# minimumSystem_Dio_Faziko_Pratama.net
KiCad netlist of a schematic drawn in EAGLE
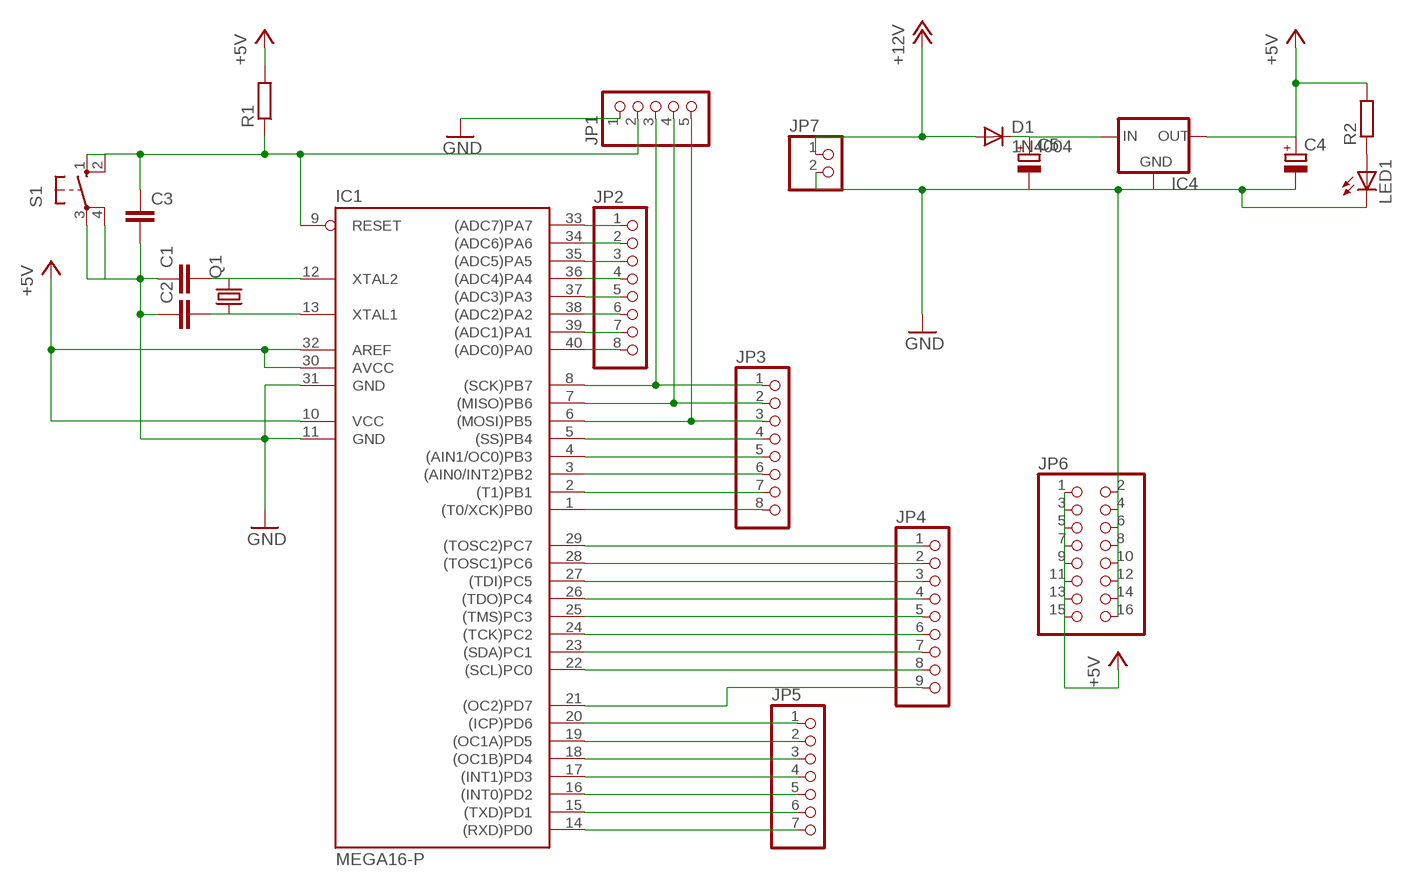
[diagram p0: schematic, sheet 1]

(export (version "E")
  (design (tool "Eeschema 10.0.6"))
  (components
    (comp (ref "C1")
      (value "C-EU025-024X044")
      (footprint "eagle-import:C025-024X044")
      (libsource (lib "eagle-import") (part "C-EU025-024X044"))
    )
    (comp (ref "C2")
      (value "C-EU025-024X044")
      (footprint "eagle-import:C025-024X044")
      (libsource (lib "eagle-import") (part "C-EU025-024X044"))
    )
    (comp (ref "C3")
      (value "C-EU050-025X075")
      (footprint "eagle-import:C050-025X075")
      (libsource (lib "eagle-import") (part "resistor_C-EU050-025X075"))
    )
    (comp (ref "C4")
      (value "CPOL-EUE2.5-5")
      (footprint "eagle-import:E2,5-5")
      (libsource (lib "eagle-import") (part "CPOL-EUE2.5-5"))
    )
    (comp (ref "C5")
      (value "CPOL-EUE2.5-5")
      (footprint "eagle-import:E2,5-5")
      (libsource (lib "eagle-import") (part "CPOL-EUE2.5-5"))
    )
    (comp (ref "D1")
      (value "1N4004")
      (footprint "eagle-import:DO41-10")
      (libsource (lib "eagle-import") (part "1N4004"))
    )
    (comp (ref "IC1")
      (value "MEGA16-P")
      (footprint "eagle-import:DIL40")
      (fields (field (name "MPN") "ATMEGA16-16PU"))
      (libsource (lib "eagle-import") (part "MEGA16-P"))
    )
    (comp (ref "IC4")
      (value "78XXS")
      (footprint "eagle-import:78XXS")
      (libsource (lib "eagle-import") (part "78XXS"))
    )
    (comp (ref "JP1")
      (value "PINHD-1X5")
      (footprint "eagle-import:1X05")
      (libsource (lib "eagle-import") (part "PINHD-1X5"))
    )
    (comp (ref "JP2")
      (value "PINHD-1X8")
      (footprint "eagle-import:1X08")
      (libsource (lib "eagle-import") (part "PINHD-1X8"))
    )
    (comp (ref "JP3")
      (value "PINHD-1X8")
      (footprint "eagle-import:1X08")
      (libsource (lib "eagle-import") (part "PINHD-1X8"))
    )
    (comp (ref "JP4")
      (value "PINHD-1X9")
      (footprint "eagle-import:1X09")
      (libsource (lib "eagle-import") (part "PINHD-1X9"))
    )
    (comp (ref "JP5")
      (value "PINHD-1X7")
      (footprint "eagle-import:1X07")
      (libsource (lib "eagle-import") (part "PINHD-1X7"))
    )
    (comp (ref "JP6")
      (value "PINHD-2X8")
      (footprint "eagle-import:2X08")
      (libsource (lib "eagle-import") (part "PINHD-2X8"))
    )
    (comp (ref "JP7")
      (value "PINHD-1X2")
      (footprint "eagle-import:1X02")
      (libsource (lib "eagle-import") (part "PINHD-1X2"))
    )
    (comp (ref "LED1")
      (value "LED5MM")
      (footprint "eagle-import:LED5MM")
      (libsource (lib "eagle-import") (part "LED5MM"))
    )
    (comp (ref "Q1")
      (value "CRYSTALHC49U-V")
      (footprint "eagle-import:HC49U-V")
      (libsource (lib "eagle-import") (part "CRYSTALHC49U-V"))
    )
    (comp (ref "R1")
      (value "R-EU_0204/7")
      (footprint "eagle-import:0204_7")
      (libsource (lib "eagle-import") (part "R-EU_0204/7"))
    )
    (comp (ref "R2")
      (value "R-EU_0204/7")
      (footprint "eagle-import:0204_7")
      (libsource (lib "eagle-import") (part "R-EU_0204/7"))
    )
    (comp (ref "S1")
      (value "10-XX")
      (footprint "eagle-import:B3F-10XX")
      (fields (field (name "MPN") "B3F-1000"))
      (libsource (lib "eagle-import") (part "10-XX"))
    )
  )
  (nets
    (net (code "1") (name "+5V") (class "Default")
      (node (ref "C4") (pin "+") (pinfunction "+_+") (pintype "passive"))
      (node (ref "IC1") (pin "10") (pinfunction "VCC_10") (pintype "power_in"))
      (node (ref "IC1") (pin "30") (pinfunction "AVCC_30") (pintype "power_in"))
      (node (ref "IC1") (pin "32") (pinfunction "AREF_32") (pintype "passive"))
      (node (ref "IC4") (pin "OUT") (pinfunction "OUT_OUT") (pintype "passive"))
      (node (ref "JP6") (pin "1") (pinfunction "1_1") (pintype "passive"))
      (node (ref "JP6") (pin "11") (pinfunction "11_11") (pintype "passive"))
      (node (ref "JP6") (pin "13") (pinfunction "13_13") (pintype "passive"))
      (node (ref "JP6") (pin "15") (pinfunction "15_15") (pintype "passive"))
      (node (ref "JP6") (pin "3") (pinfunction "3_3") (pintype "passive"))
      (node (ref "JP6") (pin "5") (pinfunction "5_5") (pintype "passive"))
      (node (ref "JP6") (pin "7") (pinfunction "7_7") (pintype "passive"))
      (node (ref "JP6") (pin "9") (pinfunction "9_9") (pintype "passive"))
      (node (ref "R1") (pin "2") (pinfunction "2_2") (pintype "passive"))
      (node (ref "R2") (pin "2") (pinfunction "2_2") (pintype "passive"))
    )
    (net (code "2") (name "+12V") (class "Default")
      (node (ref "D1") (pin "A") (pinfunction "A_A") (pintype "passive"))
      (node (ref "JP7") (pin "1") (pinfunction "1_1") (pintype "passive"))
    )
    (net (code "3") (name "GND") (class "Default")
      (node (ref "C1") (pin "1") (pinfunction "1_1") (pintype "passive"))
      (node (ref "C2") (pin "1") (pinfunction "1_1") (pintype "passive"))
      (node (ref "C3") (pin "2") (pinfunction "2_2") (pintype "passive"))
      (node (ref "C4") (pin "-") (pinfunction "-_-") (pintype "passive"))
      (node (ref "C5") (pin "-") (pinfunction "-_-") (pintype "passive"))
      (node (ref "IC1") (pin "11") (pinfunction "GND_11") (pintype "power_in"))
      (node (ref "IC1") (pin "31") (pinfunction "GND_31") (pintype "power_in"))
      (node (ref "IC4") (pin "GND") (pinfunction "GND_GND") (pintype "input"))
      (node (ref "JP1") (pin "1") (pinfunction "1_1") (pintype "passive"))
      (node (ref "JP6") (pin "10") (pinfunction "10_10") (pintype "passive"))
      (node (ref "JP6") (pin "12") (pinfunction "12_12") (pintype "passive"))
      (node (ref "JP6") (pin "14") (pinfunction "14_14") (pintype "passive"))
      (node (ref "JP6") (pin "16") (pinfunction "16_16") (pintype "passive"))
      (node (ref "JP6") (pin "2") (pinfunction "2_2") (pintype "passive"))
      (node (ref "JP6") (pin "4") (pinfunction "4_4") (pintype "passive"))
      (node (ref "JP6") (pin "6") (pinfunction "6_6") (pintype "passive"))
      (node (ref "JP6") (pin "8") (pinfunction "8_8") (pintype "passive"))
      (node (ref "JP7") (pin "2") (pinfunction "2_2") (pintype "passive"))
      (node (ref "LED1") (pin "K") (pinfunction "C_K") (pintype "passive"))
      (node (ref "S1") (pin "3") (pinfunction "P_3") (pintype "passive"))
      (node (ref "S1") (pin "4") (pinfunction "P1_4") (pintype "passive"))
    )
    (net (code "4") (name "Net-(C5-Pad+)") (class "Default")
      (node (ref "C5") (pin "+") (pinfunction "+_+") (pintype "passive"))
      (node (ref "D1") (pin "C") (pinfunction "C_C") (pintype "passive"))
      (node (ref "IC4") (pin "IN") (pinfunction "IN_IN") (pintype "input"))
    )
    (net (code "5") (name "Net-(IC1-(ADC0)PA0)") (class "Default")
      (node (ref "IC1") (pin "40") (pinfunction "(ADC0)PA0_40") (pintype "bidirectional"))
      (node (ref "JP2") (pin "8") (pinfunction "8_8") (pintype "passive"))
    )
    (net (code "6") (name "Net-(IC1-(ADC1)PA1)") (class "Default")
      (node (ref "IC1") (pin "39") (pinfunction "(ADC1)PA1_39") (pintype "bidirectional"))
      (node (ref "JP2") (pin "7") (pinfunction "7_7") (pintype "passive"))
    )
    (net (code "7") (name "Net-(IC1-(ADC2)PA2)") (class "Default")
      (node (ref "IC1") (pin "38") (pinfunction "(ADC2)PA2_38") (pintype "bidirectional"))
      (node (ref "JP2") (pin "6") (pinfunction "6_6") (pintype "passive"))
    )
    (net (code "8") (name "Net-(IC1-(ADC3)PA3)") (class "Default")
      (node (ref "IC1") (pin "37") (pinfunction "(ADC3)PA3_37") (pintype "bidirectional"))
      (node (ref "JP2") (pin "5") (pinfunction "5_5") (pintype "passive"))
    )
    (net (code "9") (name "Net-(IC1-(ADC4)PA4)") (class "Default")
      (node (ref "IC1") (pin "36") (pinfunction "(ADC4)PA4_36") (pintype "bidirectional"))
      (node (ref "JP2") (pin "4") (pinfunction "4_4") (pintype "passive"))
    )
    (net (code "10") (name "Net-(IC1-(ADC5)PA5)") (class "Default")
      (node (ref "IC1") (pin "35") (pinfunction "(ADC5)PA5_35") (pintype "bidirectional"))
      (node (ref "JP2") (pin "3") (pinfunction "3_3") (pintype "passive"))
    )
    (net (code "11") (name "Net-(IC1-(ADC6)PA6)") (class "Default")
      (node (ref "IC1") (pin "34") (pinfunction "(ADC6)PA6_34") (pintype "bidirectional"))
      (node (ref "JP2") (pin "2") (pinfunction "2_2") (pintype "passive"))
    )
    (net (code "12") (name "Net-(IC1-(ADC7)PA7)") (class "Default")
      (node (ref "IC1") (pin "33") (pinfunction "(ADC7)PA7_33") (pintype "bidirectional"))
      (node (ref "JP2") (pin "1") (pinfunction "1_1") (pintype "passive"))
    )
    (net (code "13") (name "Net-(IC1-(AIN0{slash}INT2)PB2)") (class "Default")
      (node (ref "IC1") (pin "3") (pinfunction "(AIN0/INT2)PB2_3") (pintype "bidirectional"))
      (node (ref "JP3") (pin "6") (pinfunction "6_6") (pintype "passive"))
    )
    (net (code "14") (name "Net-(IC1-(AIN1{slash}OC0)PB3)") (class "Default")
      (node (ref "IC1") (pin "4") (pinfunction "(AIN1/OC0)PB3_4") (pintype "bidirectional"))
      (node (ref "JP3") (pin "5") (pinfunction "5_5") (pintype "passive"))
    )
    (net (code "15") (name "Net-(IC1-(ICP)PD6)") (class "Default")
      (node (ref "IC1") (pin "20") (pinfunction "(ICP)PD6_20") (pintype "bidirectional"))
      (node (ref "JP5") (pin "1") (pinfunction "1_1") (pintype "passive"))
    )
    (net (code "16") (name "Net-(IC1-(INT0)PD2)") (class "Default")
      (node (ref "IC1") (pin "16") (pinfunction "(INT0)PD2_16") (pintype "bidirectional"))
      (node (ref "JP5") (pin "5") (pinfunction "5_5") (pintype "passive"))
    )
    (net (code "17") (name "Net-(IC1-(INT1)PD3)") (class "Default")
      (node (ref "IC1") (pin "17") (pinfunction "(INT1)PD3_17") (pintype "bidirectional"))
      (node (ref "JP5") (pin "4") (pinfunction "4_4") (pintype "passive"))
    )
    (net (code "18") (name "Net-(IC1-(MISO)PB6)") (class "Default")
      (node (ref "IC1") (pin "7") (pinfunction "(MISO)PB6_7") (pintype "bidirectional"))
      (node (ref "JP1") (pin "4") (pinfunction "4_4") (pintype "passive"))
      (node (ref "JP3") (pin "2") (pinfunction "2_2") (pintype "passive"))
    )
    (net (code "19") (name "Net-(IC1-(MOSI)PB5)") (class "Default")
      (node (ref "IC1") (pin "6") (pinfunction "(MOSI)PB5_6") (pintype "bidirectional"))
      (node (ref "JP1") (pin "5") (pinfunction "5_5") (pintype "passive"))
      (node (ref "JP3") (pin "3") (pinfunction "3_3") (pintype "passive"))
    )
    (net (code "20") (name "Net-(IC1-(OC1A)PD5)") (class "Default")
      (node (ref "IC1") (pin "19") (pinfunction "(OC1A)PD5_19") (pintype "bidirectional"))
      (node (ref "JP5") (pin "2") (pinfunction "2_2") (pintype "passive"))
    )
    (net (code "21") (name "Net-(IC1-(OC1B)PD4)") (class "Default")
      (node (ref "IC1") (pin "18") (pinfunction "(OC1B)PD4_18") (pintype "bidirectional"))
      (node (ref "JP5") (pin "3") (pinfunction "3_3") (pintype "passive"))
    )
    (net (code "22") (name "Net-(IC1-(OC2)PD7)") (class "Default")
      (node (ref "IC1") (pin "21") (pinfunction "(OC2)PD7_21") (pintype "bidirectional"))
      (node (ref "JP4") (pin "9") (pinfunction "9_9") (pintype "passive"))
    )
    (net (code "23") (name "Net-(IC1-(RXD)PD0)") (class "Default")
      (node (ref "IC1") (pin "14") (pinfunction "(RXD)PD0_14") (pintype "bidirectional"))
      (node (ref "JP5") (pin "7") (pinfunction "7_7") (pintype "passive"))
    )
    (net (code "24") (name "Net-(IC1-(SCK)PB7)") (class "Default")
      (node (ref "IC1") (pin "8") (pinfunction "(SCK)PB7_8") (pintype "bidirectional"))
      (node (ref "JP1") (pin "3") (pinfunction "3_3") (pintype "passive"))
      (node (ref "JP3") (pin "1") (pinfunction "1_1") (pintype "passive"))
    )
    (net (code "25") (name "Net-(IC1-(SCL)PC0)") (class "Default")
      (node (ref "IC1") (pin "22") (pinfunction "(SCL)PC0_22") (pintype "bidirectional"))
      (node (ref "JP4") (pin "8") (pinfunction "8_8") (pintype "passive"))
    )
    (net (code "26") (name "Net-(IC1-(SDA)PC1)") (class "Default")
      (node (ref "IC1") (pin "23") (pinfunction "(SDA)PC1_23") (pintype "bidirectional"))
      (node (ref "JP4") (pin "7") (pinfunction "7_7") (pintype "passive"))
    )
    (net (code "27") (name "Net-(IC1-(SS)PB4)") (class "Default")
      (node (ref "IC1") (pin "5") (pinfunction "(SS)PB4_5") (pintype "bidirectional"))
      (node (ref "JP3") (pin "4") (pinfunction "4_4") (pintype "passive"))
    )
    (net (code "28") (name "Net-(IC1-(T0{slash}XCK)PB0)") (class "Default")
      (node (ref "IC1") (pin "1") (pinfunction "(T0/XCK)PB0_1") (pintype "bidirectional"))
      (node (ref "JP3") (pin "8") (pinfunction "8_8") (pintype "passive"))
    )
    (net (code "29") (name "Net-(IC1-(T1)PB1)") (class "Default")
      (node (ref "IC1") (pin "2") (pinfunction "(T1)PB1_2") (pintype "bidirectional"))
      (node (ref "JP3") (pin "7") (pinfunction "7_7") (pintype "passive"))
    )
    (net (code "30") (name "Net-(IC1-(TCK)PC2)") (class "Default")
      (node (ref "IC1") (pin "24") (pinfunction "(TCK)PC2_24") (pintype "bidirectional"))
      (node (ref "JP4") (pin "6") (pinfunction "6_6") (pintype "passive"))
    )
    (net (code "31") (name "Net-(IC1-(TDI)PC5)") (class "Default")
      (node (ref "IC1") (pin "27") (pinfunction "(TDI)PC5_27") (pintype "bidirectional"))
      (node (ref "JP4") (pin "3") (pinfunction "3_3") (pintype "passive"))
    )
    (net (code "32") (name "Net-(IC1-(TDO)PC4)") (class "Default")
      (node (ref "IC1") (pin "26") (pinfunction "(TDO)PC4_26") (pintype "bidirectional"))
      (node (ref "JP4") (pin "4") (pinfunction "4_4") (pintype "passive"))
    )
    (net (code "33") (name "Net-(IC1-(TMS)PC3)") (class "Default")
      (node (ref "IC1") (pin "25") (pinfunction "(TMS)PC3_25") (pintype "bidirectional"))
      (node (ref "JP4") (pin "5") (pinfunction "5_5") (pintype "passive"))
    )
    (net (code "34") (name "Net-(IC1-(TOSC1)PC6)") (class "Default")
      (node (ref "IC1") (pin "28") (pinfunction "(TOSC1)PC6_28") (pintype "bidirectional"))
      (node (ref "JP4") (pin "2") (pinfunction "2_2") (pintype "passive"))
    )
    (net (code "35") (name "Net-(IC1-(TOSC2)PC7)") (class "Default")
      (node (ref "IC1") (pin "29") (pinfunction "(TOSC2)PC7_29") (pintype "bidirectional"))
      (node (ref "JP4") (pin "1") (pinfunction "1_1") (pintype "passive"))
    )
    (net (code "36") (name "Net-(IC1-(TXD)PD1)") (class "Default")
      (node (ref "IC1") (pin "15") (pinfunction "(TXD)PD1_15") (pintype "bidirectional"))
      (node (ref "JP5") (pin "6") (pinfunction "6_6") (pintype "passive"))
    )
    (net (code "37") (name "Net-(IC1-RESET)") (class "Default")
      (node (ref "C3") (pin "1") (pinfunction "1_1") (pintype "passive"))
      (node (ref "IC1") (pin "9") (pinfunction "RESET_9") (pintype "input"))
      (node (ref "JP1") (pin "2") (pinfunction "2_2") (pintype "passive"))
      (node (ref "R1") (pin "1") (pinfunction "1_1") (pintype "passive"))
      (node (ref "S1") (pin "1") (pinfunction "S_1") (pintype "passive"))
      (node (ref "S1") (pin "2") (pinfunction "S1_2") (pintype "passive"))
    )
    (net (code "38") (name "Net-(IC1-XTAL1)") (class "Default")
      (node (ref "C2") (pin "2") (pinfunction "2_2") (pintype "passive"))
      (node (ref "IC1") (pin "13") (pinfunction "XTAL1_13") (pintype "bidirectional"))
      (node (ref "Q1") (pin "1") (pinfunction "1_1") (pintype "passive"))
    )
    (net (code "39") (name "Net-(IC1-XTAL2)") (class "Default")
      (node (ref "C1") (pin "2") (pinfunction "2_2") (pintype "passive"))
      (node (ref "IC1") (pin "12") (pinfunction "XTAL2_12") (pintype "bidirectional"))
      (node (ref "Q1") (pin "2") (pinfunction "2_2") (pintype "passive"))
    )
    (net (code "40") (name "Net-(LED1-PadA)") (class "Default")
      (node (ref "LED1") (pin "A") (pinfunction "A_A") (pintype "passive"))
      (node (ref "R2") (pin "1") (pinfunction "1_1") (pintype "passive"))
    )
  )
)
